# Humidity_sensor_attiny85.net
KiCad netlist of a schematic drawn in EasyEDA
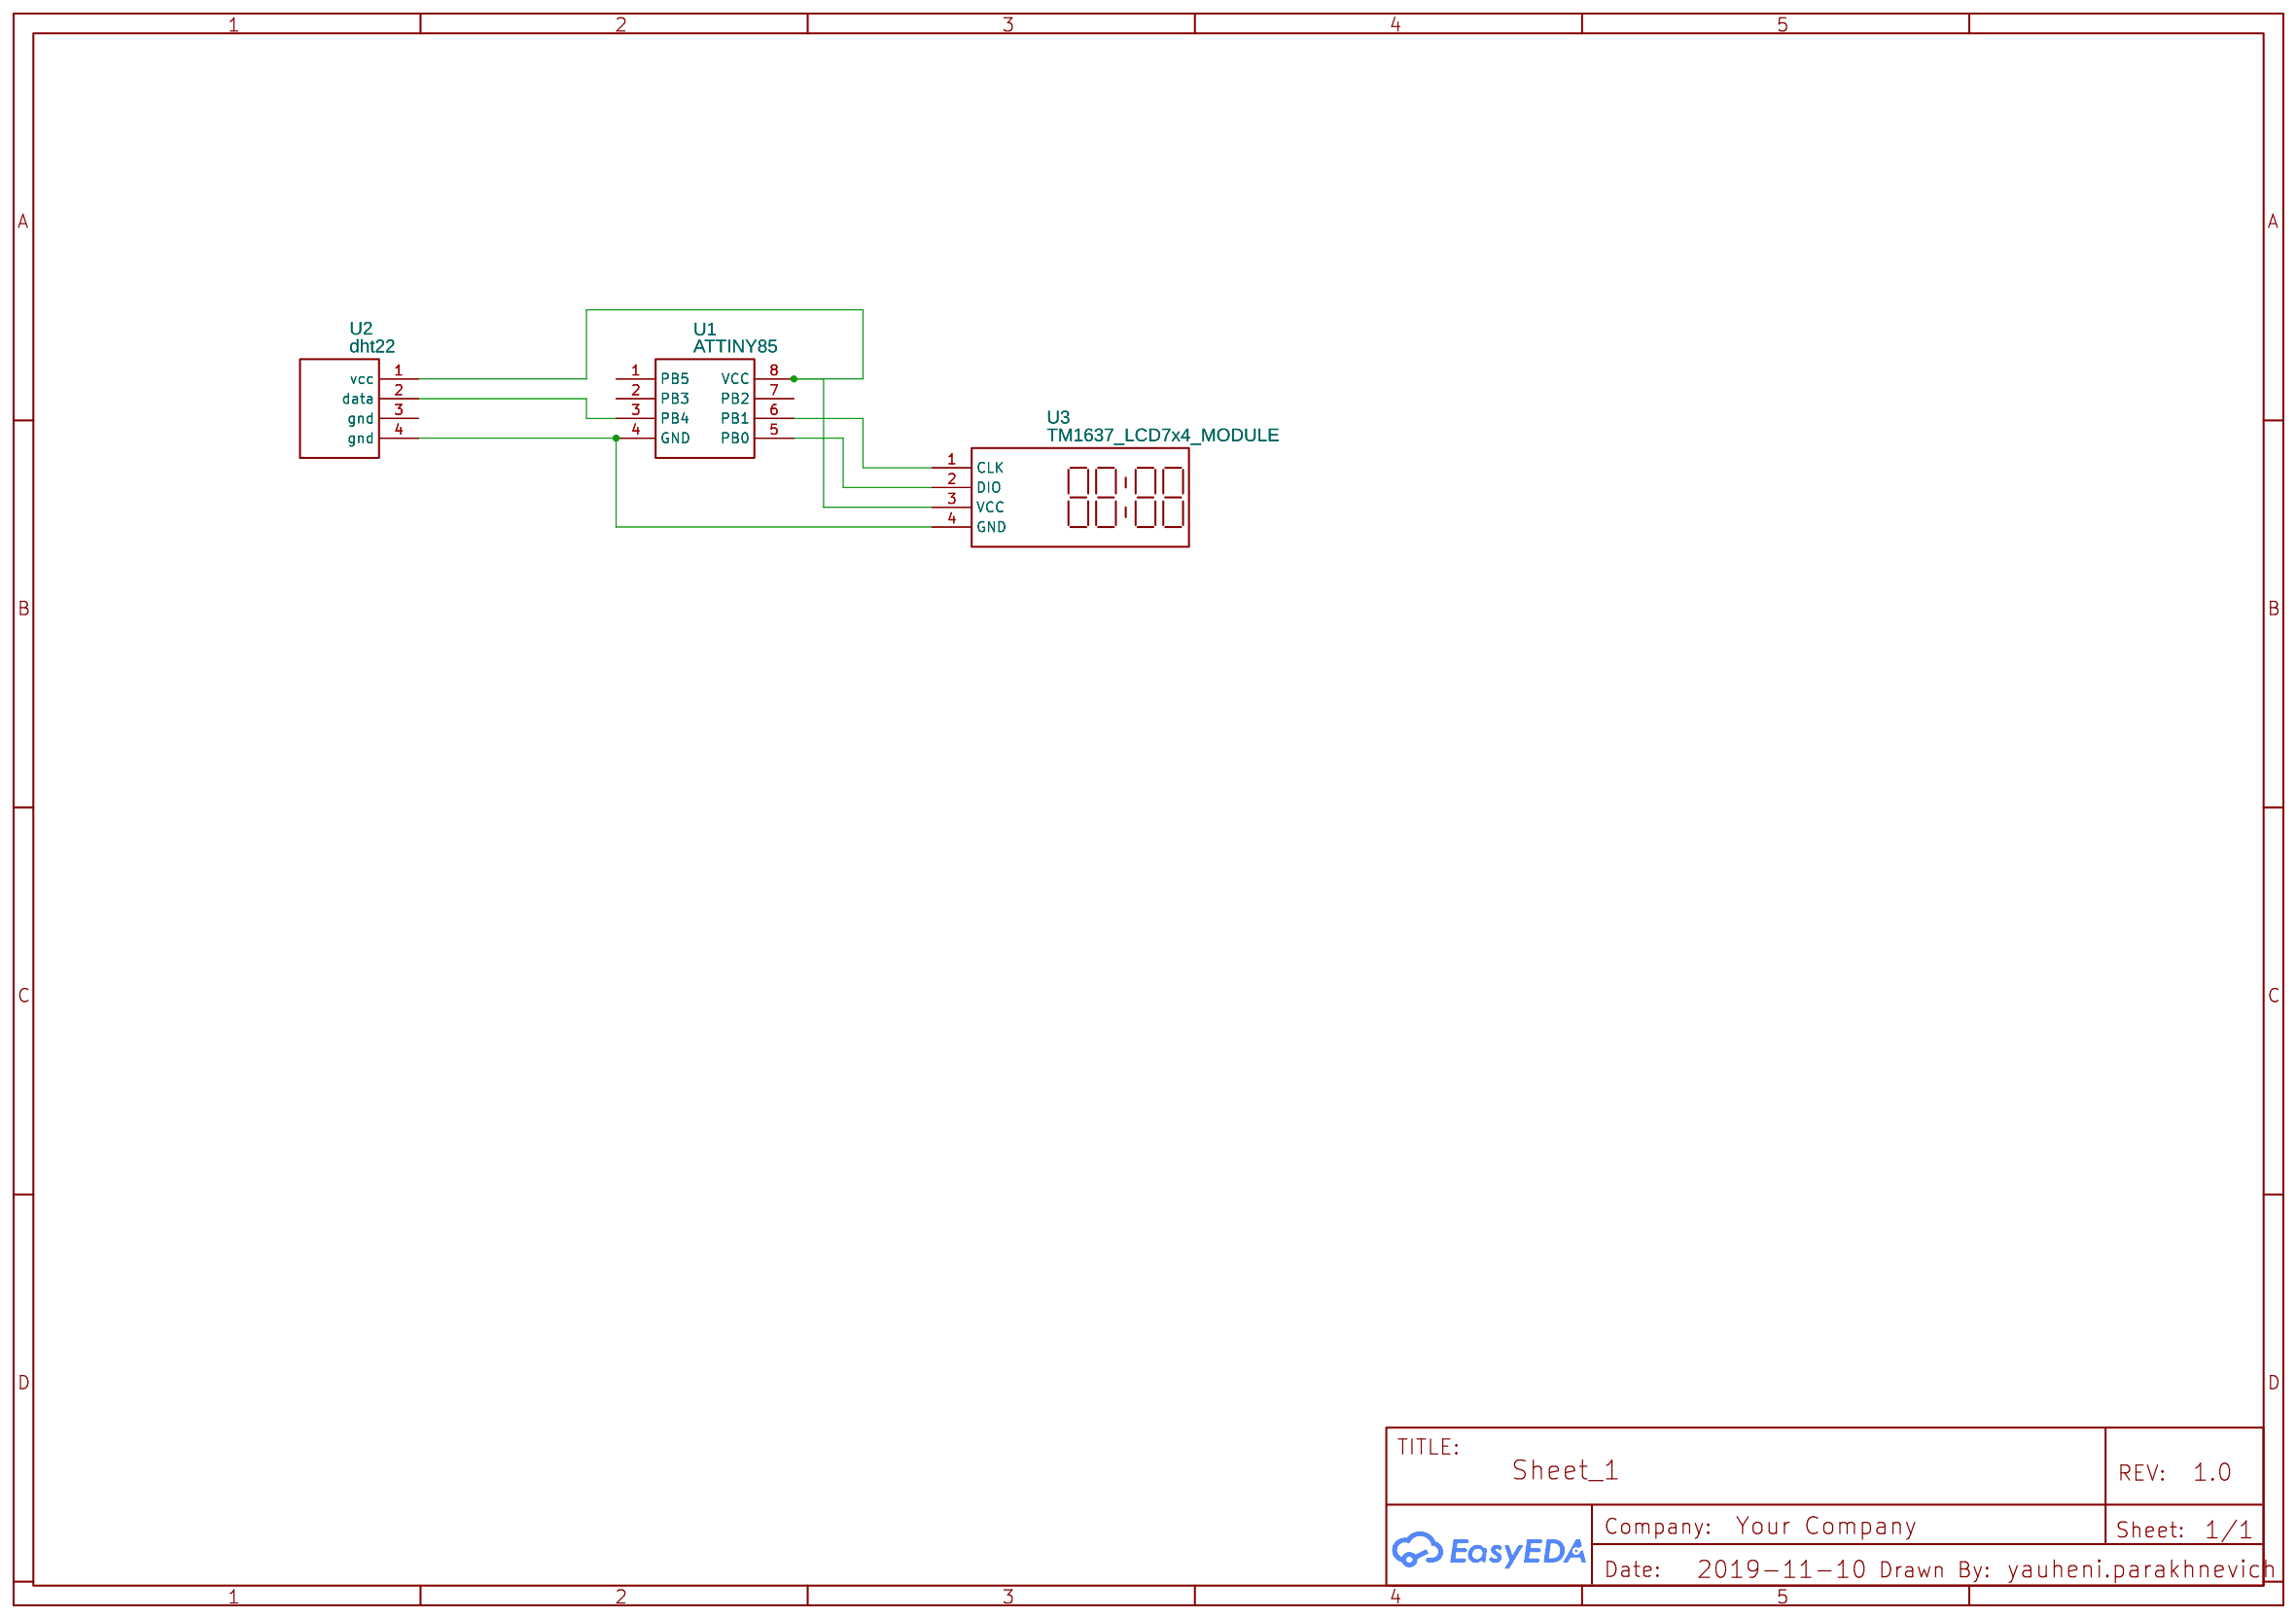
[diagram p0: schematic sheet]

(export (version "E")
  (design (tool "Eeschema 10.0.6"))
  (components
    (comp (ref "U1")
      (value "ATTINY85")
      (fields (field (name "BOM_Supplier Part") "undefined"))
      (libsource (lib "") (part "ATTINY85"))
    )
    (comp (ref "U2") (value "dht22") (libsource (lib "") (part "dht22")))
    (comp (ref "U3") (value "TM1637_LCD7x4_MODULE") (libsource (lib "") (part "TM1637_LCD7x4_MODULE")))
  )
  (nets
    (net (code "1") (name "Net-(U1-GND)") (class "Default")
      (node (ref "U1") (pin "4") (pinfunction "GND_4") (pintype "unspecified"))
      (node (ref "U2") (pin "4") (pinfunction "gnd_4") (pintype "unspecified"))
      (node (ref "U3") (pin "4") (pinfunction "GND_4") (pintype "unspecified"))
    )
    (net (code "2") (name "Net-(U1-PB0)") (class "Default")
      (node (ref "U1") (pin "5") (pinfunction "PB0_5") (pintype "unspecified"))
      (node (ref "U3") (pin "2") (pinfunction "DIO_2") (pintype "unspecified"))
    )
    (net (code "3") (name "Net-(U1-PB1)") (class "Default")
      (node (ref "U1") (pin "6") (pinfunction "PB1_6") (pintype "unspecified"))
      (node (ref "U3") (pin "1") (pinfunction "CLK_1") (pintype "unspecified"))
    )
    (net (code "4") (name "Net-(U1-PB4)") (class "Default")
      (node (ref "U1") (pin "3") (pinfunction "PB4_3") (pintype "unspecified"))
      (node (ref "U2") (pin "2") (pinfunction "data_2") (pintype "unspecified"))
    )
    (net (code "5") (name "Net-(U1-VCC)") (class "Default")
      (node (ref "U1") (pin "8") (pinfunction "VCC_8") (pintype "unspecified"))
      (node (ref "U2") (pin "1") (pinfunction "vcc_1") (pintype "unspecified"))
      (node (ref "U3") (pin "3") (pinfunction "VCC_3") (pintype "unspecified"))
    )
    (net (code "6") (name "unconnected-(U1-PB2-Pad7)") (class "Default")
      (node (ref "U1") (pin "7") (pinfunction "PB2_7") (pintype "unspecified"))
    )
    (net (code "7") (name "unconnected-(U1-PB3-Pad2)") (class "Default")
      (node (ref "U1") (pin "2") (pinfunction "PB3_2") (pintype "unspecified"))
    )
    (net (code "8") (name "unconnected-(U1-PB5-Pad1)") (class "Default")
      (node (ref "U1") (pin "1") (pinfunction "PB5_1") (pintype "unspecified"))
    )
    (net (code "9") (name "unconnected-(U2-gnd-Pad3)") (class "Default")
      (node (ref "U2") (pin "3") (pinfunction "gnd_3") (pintype "unspecified"))
    )
  )
)
